# pid.net
KiCad netlist of a schematic drawn in EAGLE
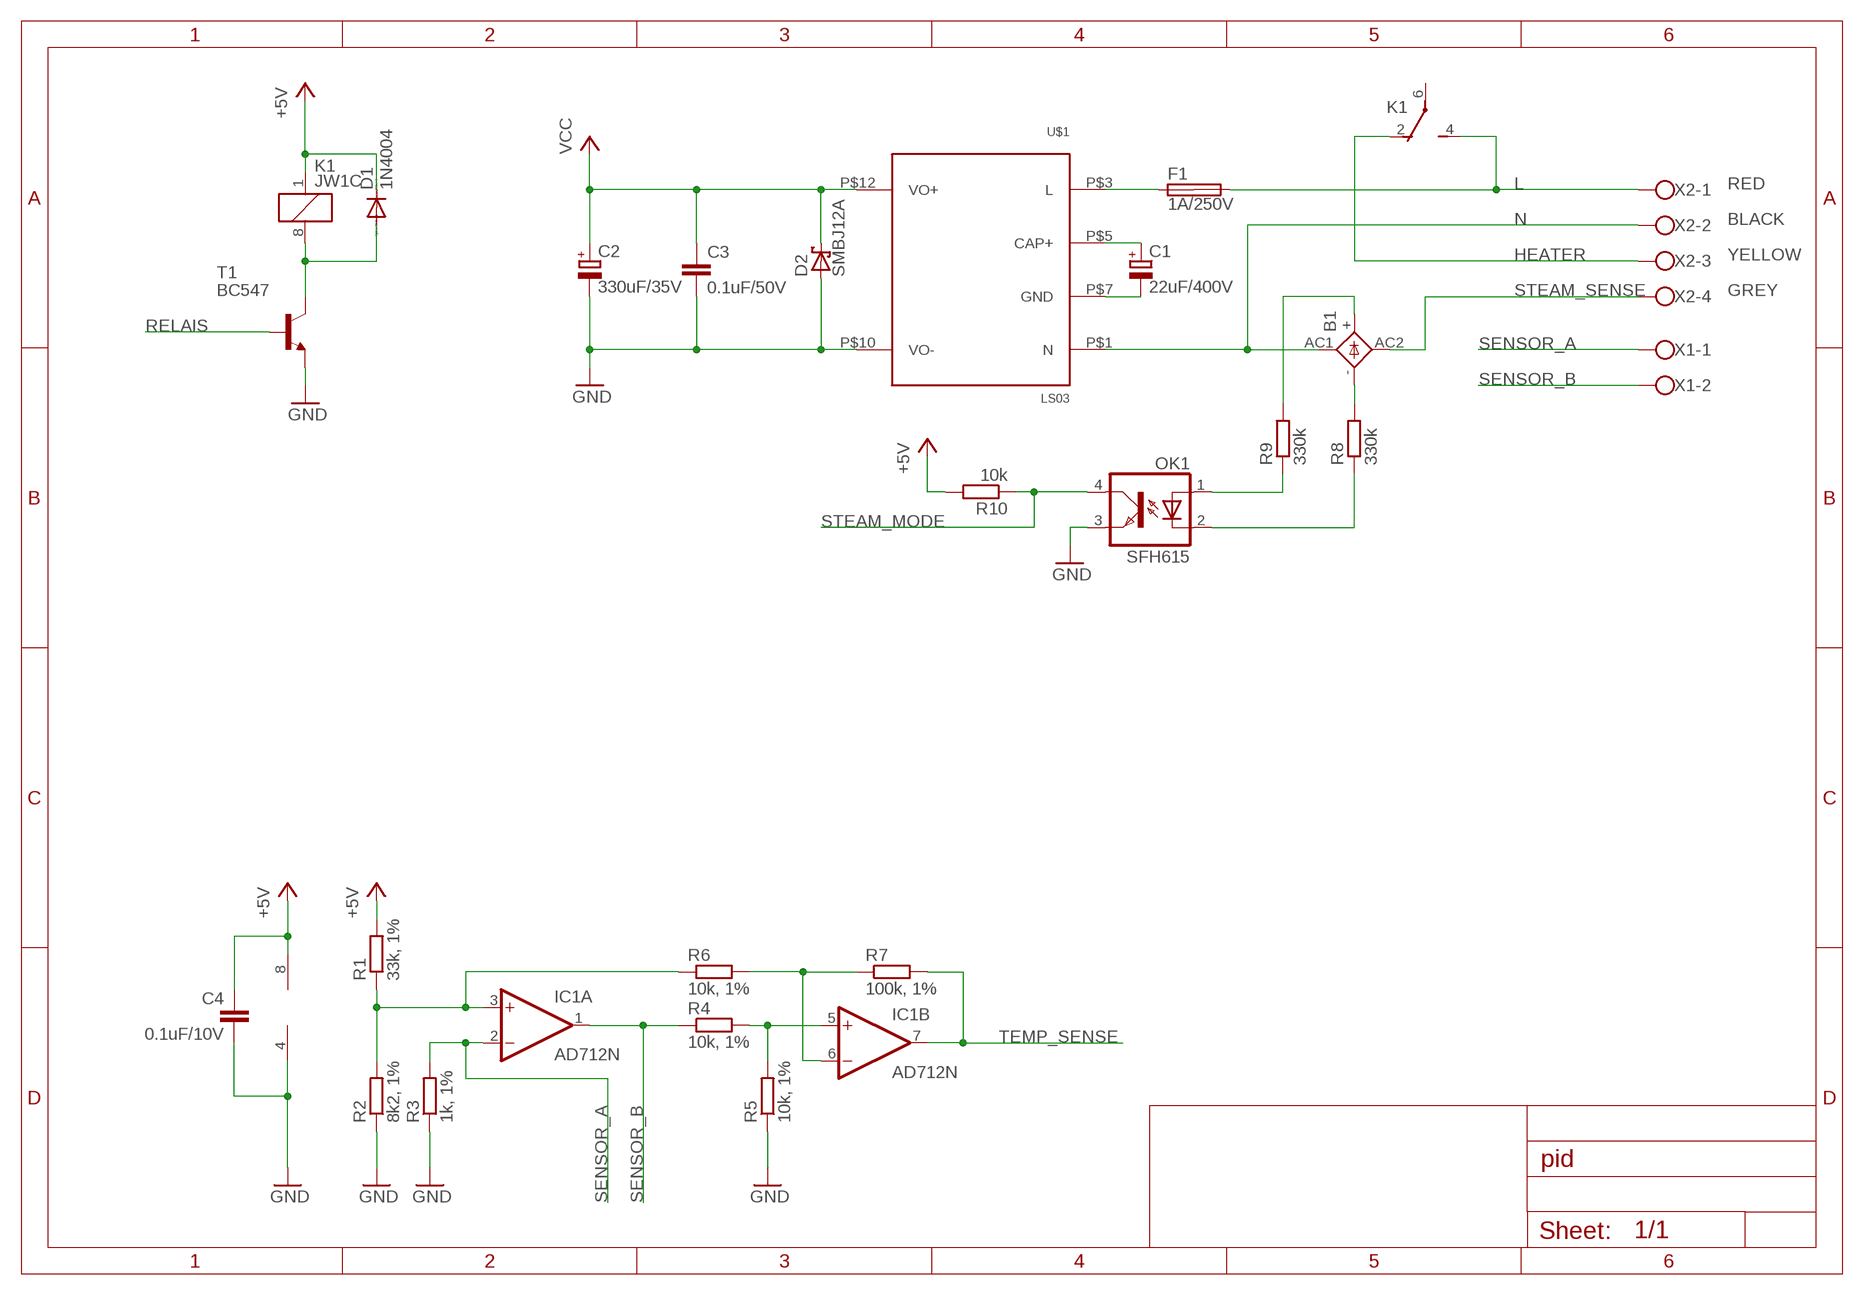
[diagram p0: schematic, sheet 1]

(export (version "E")
  (design (tool "Eeschema 10.0.6"))
  (components
    (comp (ref "B1")
      (value "1KAB")
      (footprint "eagle-import:1KAB")
      (libsource (lib "eagle-import") (part "1KAB"))
    )
    (comp (ref "C1")
      (value "22uF/400V")
      (footprint "eagle-import:E3,5-10")
      (libsource (lib "eagle-import") (part "CPOL-EUE3.5-10"))
    )
    (comp (ref "C2")
      (value "330uF/35V")
      (footprint "eagle-import:E7,5-16")
      (libsource (lib "eagle-import") (part "CPOL-EUE7.5-16"))
    )
    (comp (ref "C3")
      (value "0.1uF/50V")
      (footprint "eagle-import:C025-050X050")
      (libsource (lib "eagle-import") (part "C-EU025-050X050"))
    )
    (comp (ref "C4")
      (value "0.1uF/10V")
      (footprint "eagle-import:C025-050X050")
      (libsource (lib "eagle-import") (part "C-EU025-050X050"))
    )
    (comp (ref "D1")
      (value "1N4004")
      (footprint "eagle-import:DO41-10")
      (libsource (lib "eagle-import") (part "1N4004"))
    )
    (comp (ref "D2")
      (value "SMBJ12A")
      (footprint "eagle-import:CB417-15")
      (libsource (lib "eagle-import") (part "P6KEXX"))
    )
    (comp (ref "F1")
      (value "1A/250V")
      (footprint "eagle-import:SHK20Q")
      (libsource (lib "eagle-import") (part "SHK20Q"))
    )
    (comp (ref "IC1")
      (value "AD712N")
      (footprint "eagle-import:DIL08")
      (libsource (lib "eagle-import") (part "AD712N"))
    )
    (comp (ref "K1")
      (value "JW1C")
      (footprint "eagle-import:JW1C")
      (libsource (lib "eagle-import") (part "JW1C"))
    )
    (comp (ref "OK1")
      (value "SFH615")
      (footprint "eagle-import:DIL04")
      (fields (field (name "MPN") "SFH615A-2"))
      (libsource (lib "eagle-import") (part "SFH615"))
    )
    (comp (ref "R1")
      (value "33k, 1%")
      (footprint "eagle-import:0207_10")
      (libsource (lib "eagle-import") (part "R-EU_0207/10"))
    )
    (comp (ref "R2")
      (value "8k2, 1%")
      (footprint "eagle-import:0207_10")
      (libsource (lib "eagle-import") (part "R-EU_0207/10"))
    )
    (comp (ref "R3")
      (value "1k, 1%")
      (footprint "eagle-import:0207_10")
      (libsource (lib "eagle-import") (part "R-EU_0207/10"))
    )
    (comp (ref "R4")
      (value "10k, 1%")
      (footprint "eagle-import:0207_10")
      (libsource (lib "eagle-import") (part "R-EU_0207/10"))
    )
    (comp (ref "R5")
      (value "10k, 1%")
      (footprint "eagle-import:0207_10")
      (libsource (lib "eagle-import") (part "R-EU_0207/10"))
    )
    (comp (ref "R6")
      (value "10k, 1%")
      (footprint "eagle-import:0207_10")
      (libsource (lib "eagle-import") (part "R-EU_0207/10"))
    )
    (comp (ref "R7")
      (value "100k, 1%")
      (footprint "eagle-import:0207_10")
      (libsource (lib "eagle-import") (part "R-EU_0207/10"))
    )
    (comp (ref "R8")
      (value "330k")
      (footprint "eagle-import:0207_10")
      (libsource (lib "eagle-import") (part "R-EU_0207/10"))
    )
    (comp (ref "R9")
      (value "330k")
      (footprint "eagle-import:0207_10")
      (libsource (lib "eagle-import") (part "R-EU_0207/10"))
    )
    (comp (ref "R10")
      (value "10k")
      (footprint "eagle-import:0207_10")
      (libsource (lib "eagle-import") (part "R-EU_0207/10"))
    )
    (comp (ref "T1")
      (value "BC547")
      (footprint "eagle-import:TO92")
      (libsource (lib "eagle-import") (part "BC547"))
    )
    (comp (ref "U$1")
      (value "LS03")
      (footprint "eagle-import:LS03")
      (libsource (lib "eagle-import") (part "LS03"))
    )
    (comp (ref "X1")
      (value "W239-302")
      (footprint "eagle-import:W239-302")
      (libsource (lib "eagle-import") (part "W239-302"))
    )
    (comp (ref "X2")
      (value "W239-104")
      (footprint "eagle-import:W239-104")
      (libsource (lib "eagle-import") (part "W239-104"))
    )
  )
  (nets
    (net (code "1") (name "+5V") (class "Default")
      (node (ref "C4") (pin "1") (pinfunction "1_1") (pintype "passive"))
      (node (ref "D1") (pin "C") (pinfunction "C_C") (pintype "passive"))
      (node (ref "IC1") (pin "8") (pinfunction "V+_8") (pintype "power_in"))
      (node (ref "K1") (pin "1") (pinfunction "1_1") (pintype "passive"))
      (node (ref "R1") (pin "2") (pinfunction "2_2") (pintype "passive"))
      (node (ref "R10") (pin "2") (pinfunction "2_2") (pintype "passive"))
    )
    (net (code "2") (name "/HEATER") (class "Default")
      (node (ref "K1") (pin "2") (pinfunction "O_2") (pintype "passive"))
      (node (ref "X2") (pin "3") (pinfunction "KL_3") (pintype "passive"))
    )
    (net (code "3") (name "/L") (class "Default")
      (node (ref "F1") (pin "2A") (pinfunction "2A_2A") (pintype "passive"))
      (node (ref "K1") (pin "4") (pinfunction "S_4") (pintype "passive"))
      (node (ref "X2") (pin "1") (pinfunction "KL_1") (pintype "passive"))
    )
    (net (code "4") (name "/N") (class "Default")
      (node (ref "B1") (pin "AC1") (pinfunction "AC1_AC1") (pintype "passive"))
      (node (ref "U$1") (pin "P$1") (pinfunction "N_P$1") (pintype "bidirectional"))
      (node (ref "X2") (pin "2") (pinfunction "KL_2") (pintype "passive"))
    )
    (net (code "5") (name "/RELAIS") (class "Default")
      (node (ref "T1") (pin "2") (pinfunction "B_2") (pintype "passive"))
    )
    (net (code "6") (name "/SENSOR_A") (class "Default")
      (node (ref "IC1") (pin "2") (pinfunction "-IN_2") (pintype "input"))
      (node (ref "R3") (pin "2") (pinfunction "2_2") (pintype "passive"))
      (node (ref "X1") (pin "1") (pinfunction "KL_1") (pintype "passive"))
    )
    (net (code "7") (name "/SENSOR_B") (class "Default")
      (node (ref "IC1") (pin "1") (pinfunction "OUT_1") (pintype "output"))
      (node (ref "R4") (pin "1") (pinfunction "1_1") (pintype "passive"))
      (node (ref "X1") (pin "2") (pinfunction "KL_2") (pintype "passive"))
    )
    (net (code "8") (name "/STEAM_MODE") (class "Default")
      (node (ref "OK1") (pin "4") (pinfunction "COL_4") (pintype "passive"))
      (node (ref "R10") (pin "1") (pinfunction "1_1") (pintype "passive"))
    )
    (net (code "9") (name "/STEAM_SENSE") (class "Default")
      (node (ref "B1") (pin "AC2") (pinfunction "AC2_AC2") (pintype "passive"))
      (node (ref "X2") (pin "4") (pinfunction "KL_4") (pintype "passive"))
    )
    (net (code "10") (name "/TEMP_SENSE") (class "Default")
      (node (ref "IC1") (pin "7") (pinfunction "OUT_7") (pintype "output"))
      (node (ref "R7") (pin "2") (pinfunction "2_2") (pintype "passive"))
    )
    (net (code "11") (name "GND") (class "Default")
      (node (ref "C2") (pin "-") (pinfunction "-_-") (pintype "passive"))
      (node (ref "C3") (pin "2") (pinfunction "2_2") (pintype "passive"))
      (node (ref "C4") (pin "2") (pinfunction "2_2") (pintype "passive"))
      (node (ref "D2") (pin "A") (pinfunction "A_A") (pintype "passive"))
      (node (ref "IC1") (pin "4") (pinfunction "V-_4") (pintype "power_in"))
      (node (ref "OK1") (pin "3") (pinfunction "EMIT_3") (pintype "passive"))
      (node (ref "R2") (pin "1") (pinfunction "1_1") (pintype "passive"))
      (node (ref "R3") (pin "1") (pinfunction "1_1") (pintype "passive"))
      (node (ref "R5") (pin "1") (pinfunction "1_1") (pintype "passive"))
      (node (ref "T1") (pin "1") (pinfunction "E_1") (pintype "passive"))
      (node (ref "U$1") (pin "P$10") (pinfunction "VO-_P$10") (pintype "bidirectional"))
    )
    (net (code "12") (name "Net-(B1-Pad+)") (class "Default")
      (node (ref "B1") (pin "+") (pinfunction "+_+") (pintype "passive"))
      (node (ref "R9") (pin "2") (pinfunction "2_2") (pintype "passive"))
    )
    (net (code "13") (name "Net-(B1-Pad-)") (class "Default")
      (node (ref "B1") (pin "-") (pinfunction "-_-") (pintype "passive"))
      (node (ref "R8") (pin "2") (pinfunction "2_2") (pintype "passive"))
    )
    (net (code "14") (name "Net-(IC1A-+IN)") (class "Default")
      (node (ref "IC1") (pin "3") (pinfunction "+IN_3") (pintype "input"))
      (node (ref "R1") (pin "1") (pinfunction "1_1") (pintype "passive"))
      (node (ref "R2") (pin "2") (pinfunction "2_2") (pintype "passive"))
      (node (ref "R6") (pin "1") (pinfunction "1_1") (pintype "passive"))
    )
    (net (code "15") (name "Net-(IC1B-+IN)") (class "Default")
      (node (ref "IC1") (pin "5") (pinfunction "+IN_5") (pintype "input"))
      (node (ref "R4") (pin "2") (pinfunction "2_2") (pintype "passive"))
      (node (ref "R5") (pin "2") (pinfunction "2_2") (pintype "passive"))
    )
    (net (code "16") (name "Net-(IC1B--IN)") (class "Default")
      (node (ref "IC1") (pin "6") (pinfunction "-IN_6") (pintype "input"))
      (node (ref "R6") (pin "2") (pinfunction "2_2") (pintype "passive"))
      (node (ref "R7") (pin "1") (pinfunction "1_1") (pintype "passive"))
    )
    (net (code "17") (name "Net-(K1B-2)") (class "Default")
      (node (ref "D1") (pin "A") (pinfunction "A_A") (pintype "passive"))
      (node (ref "K1") (pin "8") (pinfunction "2_8") (pintype "passive"))
      (node (ref "T1") (pin "3") (pinfunction "C_3") (pintype "passive"))
    )
    (net (code "18") (name "Net-(OK1-A)") (class "Default")
      (node (ref "OK1") (pin "1") (pinfunction "A_1") (pintype "passive"))
      (node (ref "R9") (pin "1") (pinfunction "1_1") (pintype "passive"))
    )
    (net (code "19") (name "Net-(OK1-C)") (class "Default")
      (node (ref "OK1") (pin "2") (pinfunction "C_2") (pintype "passive"))
      (node (ref "R8") (pin "1") (pinfunction "1_1") (pintype "passive"))
    )
    (net (code "20") (name "Net-(U$1-CAP+)") (class "Default")
      (node (ref "C1") (pin "+") (pinfunction "+_+") (pintype "passive"))
      (node (ref "U$1") (pin "P$5") (pinfunction "CAP+_P$5") (pintype "bidirectional"))
    )
    (net (code "21") (name "Net-(U$1-GND)") (class "Default")
      (node (ref "C1") (pin "-") (pinfunction "-_-") (pintype "passive"))
      (node (ref "U$1") (pin "P$7") (pinfunction "GND_P$7") (pintype "bidirectional"))
    )
    (net (code "22") (name "Net-(U$1-L)") (class "Default")
      (node (ref "F1") (pin "1A") (pinfunction "1A_1A") (pintype "passive"))
      (node (ref "U$1") (pin "P$3") (pinfunction "L_P$3") (pintype "bidirectional"))
    )
    (net (code "23") (name "VCC") (class "Default")
      (node (ref "C2") (pin "+") (pinfunction "+_+") (pintype "passive"))
      (node (ref "C3") (pin "1") (pinfunction "1_1") (pintype "passive"))
      (node (ref "D2") (pin "C") (pinfunction "C_C") (pintype "passive"))
      (node (ref "U$1") (pin "P$12") (pinfunction "VO+_P$12") (pintype "bidirectional"))
    )
    (net (code "24") (name "unconnected-(F1-Pad1B)") (class "Default")
      (node (ref "F1") (pin "1B") (pinfunction "1B_1B") (pintype "passive"))
    )
    (net (code "25") (name "unconnected-(F1-Pad2B)") (class "Default")
      (node (ref "F1") (pin "2B") (pinfunction "2B_2B") (pintype "passive"))
    )
    (net (code "26") (name "unconnected-(K1A-P-Pad6)") (class "Default")
      (node (ref "K1") (pin "6") (pinfunction "P_6") (pintype "passive"))
    )
  )
)
